# Peripheral.net
KiCad netlist of a schematic drawn in Altium Designer
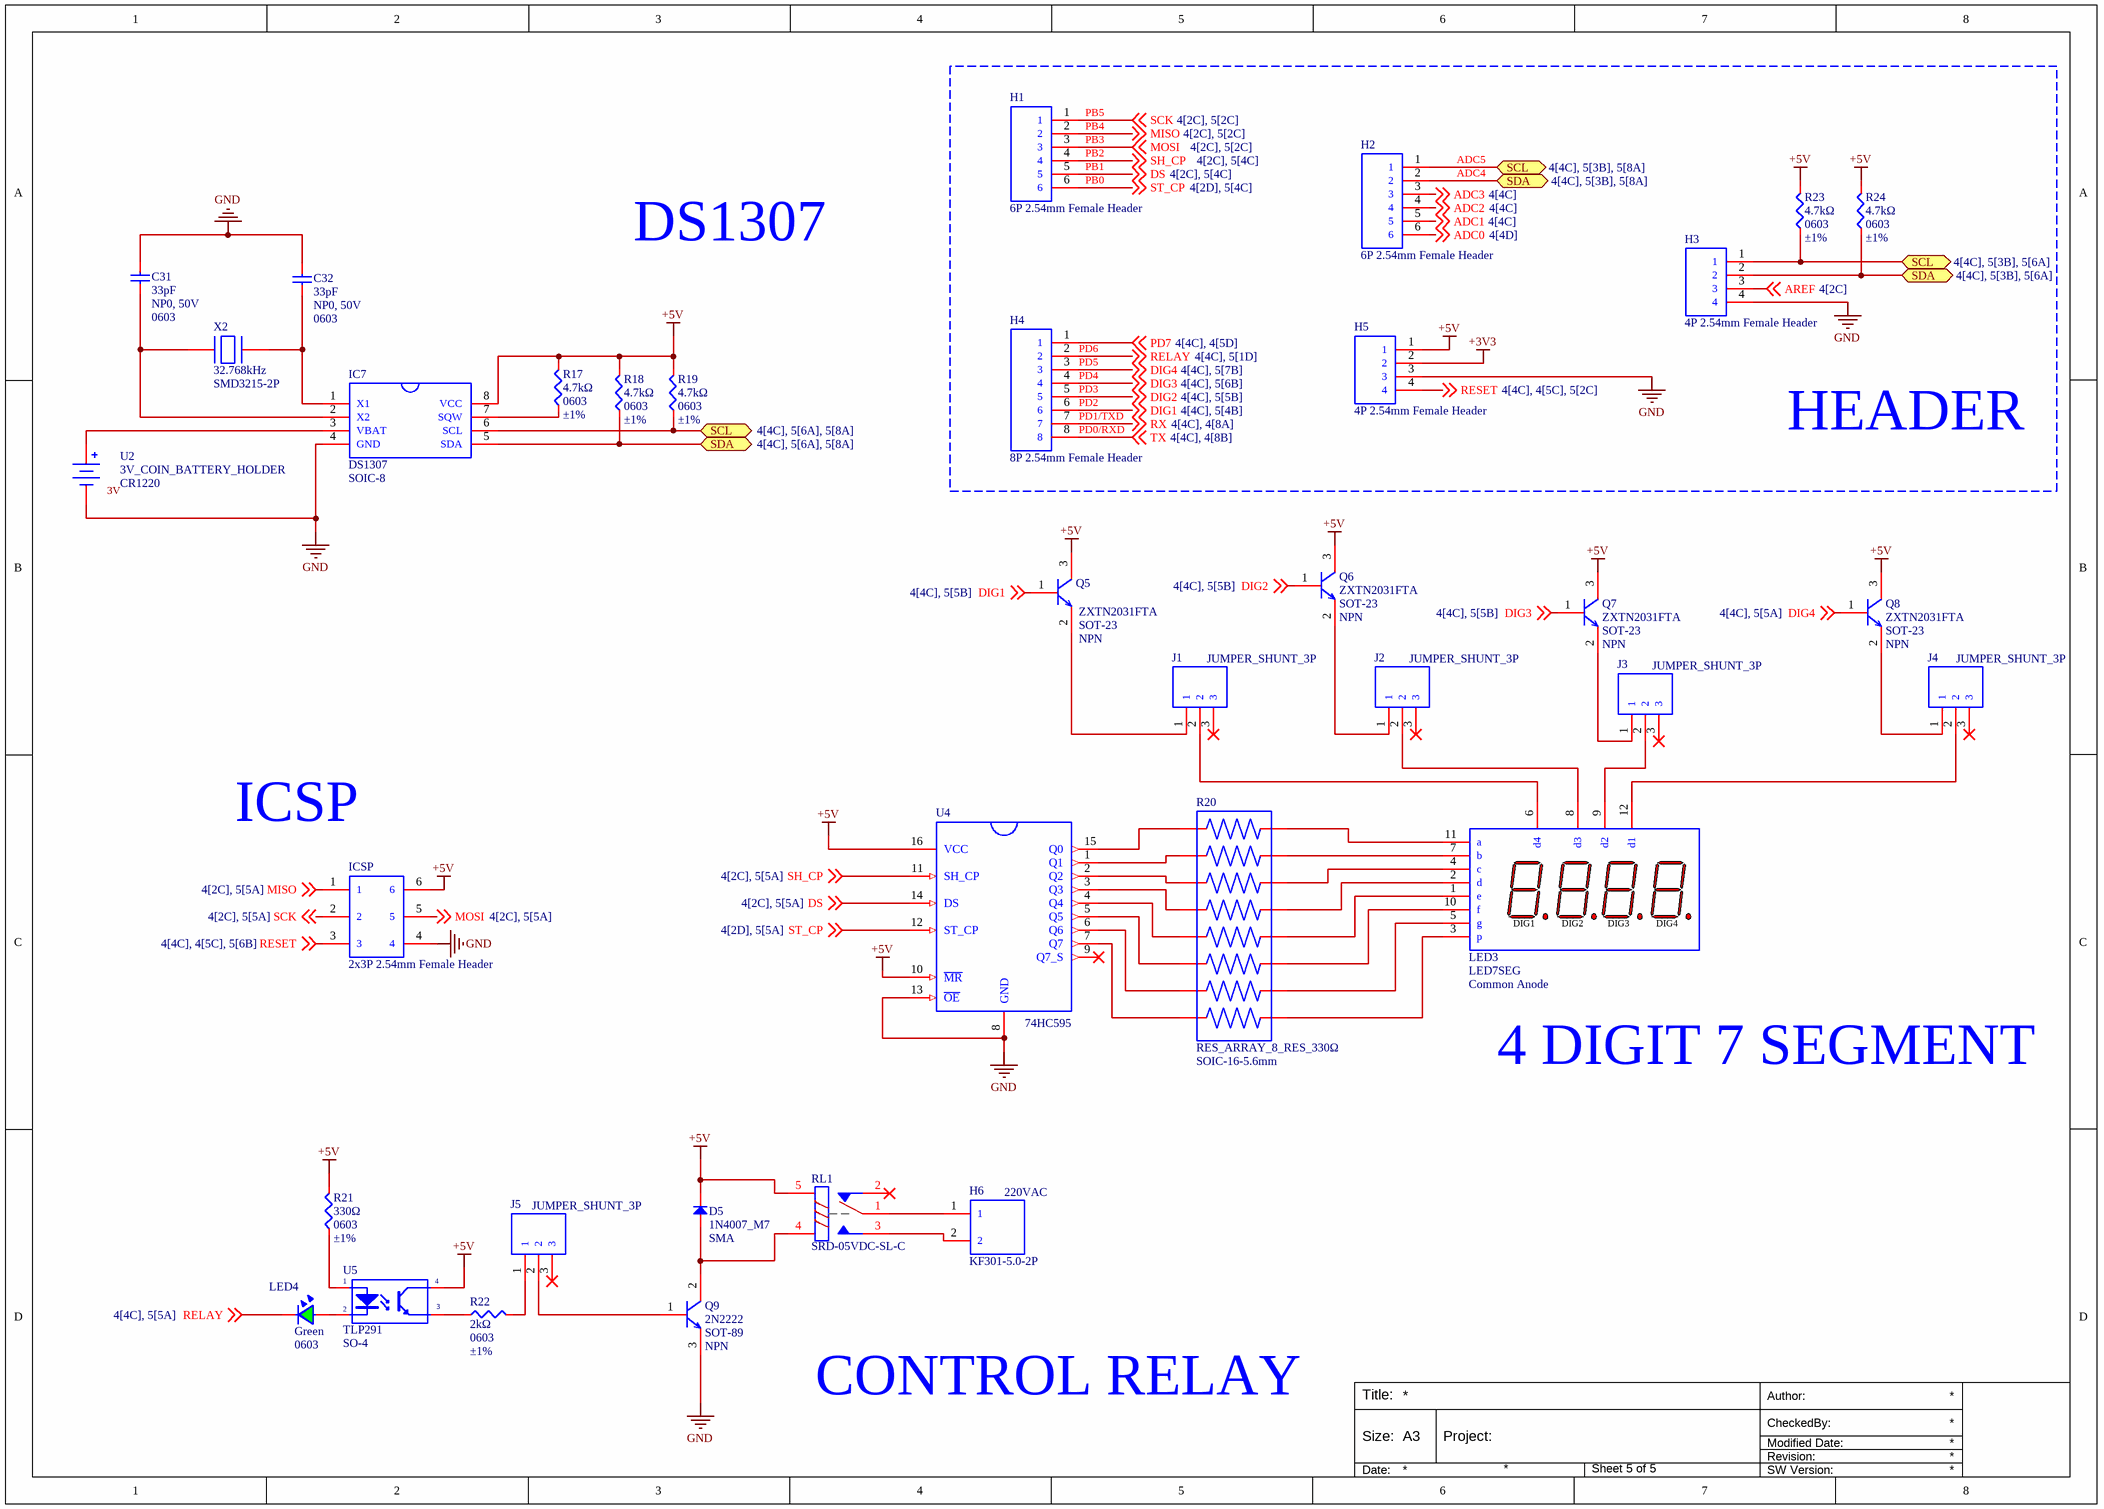
[diagram p0: Peripheral.SchDoc]

(export (version "E")
  (design (tool "Eeschema 10.0.6"))
  (components
    (comp (ref "C31")
      (value "33pF")
      (footprint "C0603")
      (description "50V 33pF NP0 ±5% 0603 Multilayer Ceramic Capacitors MLCC - SMD/SMT ROHS")
      (fields
        (field (name "MANUFACTURER") "YAGEO")
        (field (name "MFR. PART") "CC0603JRNPO9BN330")
        (field (name "TEMPERATURE COEFFICIENT") "NP0, 50V")
        (field (name "PACKAGE") "0603")
      )
      (libsource (lib "Capacitor") (part "C0603_MLCC_33pF_NP0_50V"))
    )
    (comp (ref "C32")
      (value "33pF")
      (footprint "C0603")
      (description "50V 33pF NP0 ±5% 0603 Multilayer Ceramic Capacitors MLCC - SMD/SMT ROHS")
      (fields
        (field (name "MANUFACTURER") "YAGEO")
        (field (name "MFR. PART") "CC0603JRNPO9BN330")
        (field (name "TEMPERATURE COEFFICIENT") "NP0, 50V")
        (field (name "PACKAGE") "0603")
      )
      (libsource (lib "Capacitor") (part "C0603_MLCC_33pF_NP0_50V"))
    )
    (comp (ref "D5")
      (value "1N4007_M7")
      (footprint "SMA(DO-214AC)")
      (description "1A 1V@1A 1kV SMA Diodes - General Purpose ROHS")
      (fields
        (field (name "MANUFACTURER") "JSMSEMI")
        (field (name "MFR. PART") "1N4007 M7")
        (field (name "PACKAGE") "SMA")
      )
      (libsource (lib "DIODE") (part "1N4007_M7"))
    )
    (comp (ref "H1")
      (value "6P 2.54mm Female Header")
      (footprint "6P, 2,54mm, FEMALE HEADER")
      (description "2.54mm 1 6P Through Hole 1x6P Through Hole,P=2.54mm Female Headers ROHS")
      (fields
        (field (name "MANUFACTURER") "BOOMELE(Boom Precision Elec)")
        (field (name "MFR. PART") "2.54-1*6P")
      )
      (libsource (lib "HEADER") (part "6P 2.54mm Female Header"))
    )
    (comp (ref "H2")
      (value "6P 2.54mm Female Header")
      (footprint "6P, 2,54mm, FEMALE HEADER")
      (description "2.54mm 1 6P Through Hole 1x6P Through Hole,P=2.54mm Female Headers ROHS")
      (fields
        (field (name "MANUFACTURER") "BOOMELE(Boom Precision Elec)")
        (field (name "MFR. PART") "2.54-1*6P")
      )
      (libsource (lib "HEADER") (part "6P 2.54mm Female Header"))
    )
    (comp (ref "H3")
      (value "4P 2.54mm Female Header")
      (footprint "4P, 2,54mm, FEMALE HEADER")
      (fields
        (field (name "MANUFACTURER") "BOOMELE(Boom Precision Elec)")
        (field (name "MFR. PART") "2.54-1*4P")
        (field (name "LCSC PART") "C2718488")
      )
      (libsource (lib "HEADER") (part "4P 2.54mm Female Header"))
    )
    (comp (ref "H4")
      (value "8P 2.54mm Female Header")
      (footprint "8P, 2,54mm, FEMALE HEADER")
      (description "2.54mm 1 8P Through Hole 1x8P Through Hole,P=2.54mm Female Headers ROHS")
      (fields
        (field (name "MANUFACTURER") "BOOMELE(Boom Precision Elec)")
        (field (name "MFR. PART") "2.54-1*8P")
      )
      (libsource (lib "HEADER") (part "8P 2.54mm Female Header"))
    )
    (comp (ref "H5")
      (value "4P 2.54mm Female Header")
      (footprint "4P, 2,54mm, FEMALE HEADER")
      (fields
        (field (name "MANUFACTURER") "BOOMELE(Boom Precision Elec)")
        (field (name "MFR. PART") "2.54-1*4P")
        (field (name "LCSC PART") "C2718488")
      )
      (libsource (lib "HEADER") (part "4P 2.54mm Female Header"))
    )
    (comp (ref "H6")
      (value "KF301-5.0-2P")
      (footprint "CONN-TH_P5.00_KF301-5.0-2P")
      (fields
        (field (name "MANUFACTURER") "Cixi Kefa Elec")
        (field (name "LCSC PART") "C474881")
        (field (name "CONFIGURE") "220VAC")
      )
      (libsource (lib "CONNECTER") (part "KF301-5.0-2P"))
    )
    (comp (ref "IC7")
      (value "DS1307")
      (footprint "SOIC-8")
      (description "I2C SOIC-8 Real Time Clocks ROHS")
      (fields
        (field (name "MANUFACTURER") "MAXIM")
        (field (name "MFR. PART") "DS1307Z+T&R")
        (field (name "PACKAGE") "SOIC-8")
      )
      (libsource (lib "IC") (part "DS1307-SOIC8"))
    )
    (comp (ref "ICSP")
      (value "2x3P 2.54mm Female Header")
      (footprint "2x3P, 2.54mm, Female Header")
      (fields
        (field (name "MANUFACTURER") "HanElectricity")
        (field (name "MFR. PART") "2541FV-2x3P")
        (field (name "LCSC PART") "C18723054")
      )
      (libsource (lib "HEADER") (part "2x3P 2.54mm Female Header"))
    )
    (comp (ref "J1")
      (value "JUMPER_SHUNT_3P")
      (footprint "JUMPER_SHUNT_3P")
      (fields
        (field (name "MANUFACTURER") "XFCN")
        (field (name "MFR. PART") "PZ254V-11-03P")
        (field (name "LCSC PART") "C2937625")
      )
      (libsource (lib "JUMP") (part "JUMPER_SHUNT_3P"))
    )
    (comp (ref "J2")
      (value "JUMPER_SHUNT_3P")
      (footprint "JUMPER_SHUNT_3P")
      (fields
        (field (name "MANUFACTURER") "XFCN")
        (field (name "MFR. PART") "PZ254V-11-03P")
        (field (name "LCSC PART") "C2937625")
      )
      (libsource (lib "JUMP") (part "JUMPER_SHUNT_3P"))
    )
    (comp (ref "J3")
      (value "JUMPER_SHUNT_3P")
      (footprint "JUMPER_SHUNT_3P")
      (fields
        (field (name "MANUFACTURER") "XFCN")
        (field (name "MFR. PART") "PZ254V-11-03P")
        (field (name "LCSC PART") "C2937625")
      )
      (libsource (lib "JUMP") (part "JUMPER_SHUNT_3P"))
    )
    (comp (ref "J4")
      (value "JUMPER_SHUNT_3P")
      (footprint "JUMPER_SHUNT_3P")
      (fields
        (field (name "MANUFACTURER") "XFCN")
        (field (name "MFR. PART") "PZ254V-11-03P")
        (field (name "LCSC PART") "C2937625")
      )
      (libsource (lib "JUMP") (part "JUMPER_SHUNT_3P"))
    )
    (comp (ref "J5")
      (value "JUMPER_SHUNT_3P")
      (footprint "JUMPER_SHUNT_3P")
      (fields
        (field (name "MANUFACTURER") "XFCN")
        (field (name "MFR. PART") "PZ254V-11-03P")
        (field (name "LCSC PART") "C2937625")
      )
      (libsource (lib "JUMP") (part "JUMPER_SHUNT_3P"))
    )
    (comp (ref "LED3")
      (value "LED7SEG")
      (footprint "LED7SEG_4")
      (description "Red 4 Common Anode 0.56 Through Hole LED Segment Displays ROHS")
      (fields
        (field (name "MANUFACTURER") "ZHIHAO")
        (field (name "MFR. PART") "FJ5461BH")
        (field (name "LED POLARITY") "Common Anode")
      )
      (libsource (lib "LED") (part "LED7SEG_Common_Anode"))
    )
    (comp (ref "LED4")
      (value "Green")
      (footprint "LED0603_GREEN")
      (fields
        (field (name "MANUFACTURER") "Kingbright")
        (field (name "MFR. PART") "KPT-1608LVZGCK")
        (field (name "LCSC PART") "C598356")
        (field (name "PACKAGE") "0603")
      )
      (libsource (lib "LED") (part "LED0603_Green"))
    )
    (comp (ref "Q5")
      (value "ZXTN2031FTA")
      (footprint "SOT-23")
      (description "50V 200@2A,2V 1.2W 5A NPN SOT-23 Bipolar (BJT) ROHS")
      (fields
        (field (name "MANUFACTURER") "DIODES")
        (field (name "LCSC PART") "C92166")
        (field (name "PACKAGE") "SOT-23")
        (field (name "TYPE") "NPN")
      )
      (libsource (lib "BJT and FET") (part "ZXTN2031FTA"))
    )
    (comp (ref "Q6")
      (value "ZXTN2031FTA")
      (footprint "SOT-23")
      (description "50V 200@2A,2V 1.2W 5A NPN SOT-23 Bipolar (BJT) ROHS")
      (fields
        (field (name "MANUFACTURER") "DIODES")
        (field (name "LCSC PART") "C92166")
        (field (name "PACKAGE") "SOT-23")
        (field (name "TYPE") "NPN")
      )
      (libsource (lib "BJT and FET") (part "ZXTN2031FTA"))
    )
    (comp (ref "Q7")
      (value "ZXTN2031FTA")
      (footprint "SOT-23")
      (description "50V 200@2A,2V 1.2W 5A NPN SOT-23 Bipolar (BJT) ROHS")
      (fields
        (field (name "MANUFACTURER") "DIODES")
        (field (name "LCSC PART") "C92166")
        (field (name "PACKAGE") "SOT-23")
        (field (name "TYPE") "NPN")
      )
      (libsource (lib "BJT and FET") (part "ZXTN2031FTA"))
    )
    (comp (ref "Q8")
      (value "ZXTN2031FTA")
      (footprint "SOT-23")
      (description "50V 200@2A,2V 1.2W 5A NPN SOT-23 Bipolar (BJT) ROHS")
      (fields
        (field (name "MANUFACTURER") "DIODES")
        (field (name "LCSC PART") "C92166")
        (field (name "PACKAGE") "SOT-23")
        (field (name "TYPE") "NPN")
      )
      (libsource (lib "BJT and FET") (part "ZXTN2031FTA"))
    )
    (comp (ref "Q9")
      (value "2N2222")
      (footprint "SOT-89-3L")
      (description "40V 500mW 600mA NPN SOT-89 Bipolar (BJT) ROHS")
      (fields
        (field (name "MANUFACTURER") "CBI")
        (field (name "MFR. PART") "2N2222AU")
        (field (name "PACKAGE") "SOT-89")
        (field (name "TYPE") "NPN")
      )
      (libsource (lib "BJT and FET") (part "2N2222_SOT-89"))
    )
    (comp (ref "R17")
      (value "4.7kΩ")
      (footprint "R0603")
      (description "100mW Thick Film Resistor 75V ±100ppm/℃ ±1% 4.7kΩ 0603 Chip Resistor - Surface Mount ROHS")
      (fields
        (field (name "MANUFACTURER") "YAGEO")
        (field (name "MFR. PART") "RC0603FR-074K7L")
        (field (name "PACKAGE") "0603")
        (field (name "TOLERANCE") "±1%")
      )
      (libsource (lib "Resistor") (part "R0603_4.7kΩ_±1%"))
    )
    (comp (ref "R18")
      (value "4.7kΩ")
      (footprint "R0603")
      (description "100mW Thick Film Resistor 75V ±100ppm/℃ ±1% 4.7kΩ 0603 Chip Resistor - Surface Mount ROHS")
      (fields
        (field (name "MANUFACTURER") "YAGEO")
        (field (name "MFR. PART") "RC0603FR-074K7L")
        (field (name "PACKAGE") "0603")
        (field (name "TOLERANCE") "±1%")
      )
      (libsource (lib "Resistor") (part "R0603_4.7kΩ_±1%"))
    )
    (comp (ref "R19")
      (value "4.7kΩ")
      (footprint "R0603")
      (description "100mW Thick Film Resistor 75V ±100ppm/℃ ±1% 4.7kΩ 0603 Chip Resistor - Surface Mount ROHS")
      (fields
        (field (name "MANUFACTURER") "YAGEO")
        (field (name "MFR. PART") "RC0603FR-074K7L")
        (field (name "PACKAGE") "0603")
        (field (name "TOLERANCE") "±1%")
      )
      (libsource (lib "Resistor") (part "R0603_4.7kΩ_±1%"))
    )
    (comp (ref "R20")
      (value "RES_ARRAY_8_RES_330Ω")
      (footprint "SOIC-16-5.6mm")
      (description "8 ±2% 330Ω 160mW ±100ppm/℃ SOIC-16-5.6mm Resistor Networks, Arrays ROHS")
      (fields
        (field (name "MANUFACTURER") "BOURNS")
        (field (name "TOLERANCE") "±2%")
        (field (name "PACKAGE") "SOIC-16-5.6mm")
      )
      (libsource (lib "Resistor") (part "RES_ARRAY_8_RES_330Ω"))
    )
    (comp (ref "R21")
      (value "330Ω")
      (footprint "R0603")
      (description "100mW Thick Film Resistor 75V ±100ppm/℃ ±1% 330Ω 0603 Chip Resistor - Surface Mount ROHS")
      (fields
        (field (name "MANUFACTURER") "YAGEO")
        (field (name "MFR. PART") "RC0603FR-07330RL")
        (field (name "PACKAGE") "0603")
        (field (name "TOLERANCE") "±1%")
      )
      (libsource (lib "Resistor") (part "R0603_330Ω_±1%"))
    )
    (comp (ref "R22")
      (value "2kΩ")
      (footprint "R0603")
      (description "100mW Thick Film Resistor 75V ±100ppm/℃ ±1% 2kΩ 0603 Chip Resistor - Surface Mount ROHS")
      (fields
        (field (name "MANUFACTURER") "YAGEO")
        (field (name "MFR. PART") "RC0603FR-072KL")
        (field (name "PACKAGE") "0603")
        (field (name "TOLERANCE") "±1%")
      )
      (libsource (lib "Resistor") (part "R0603_2kΩ_±1%"))
    )
    (comp (ref "R23")
      (value "4.7kΩ")
      (footprint "R0603")
      (description "100mW Thick Film Resistor 75V ±100ppm/℃ ±1% 4.7kΩ 0603 Chip Resistor - Surface Mount ROHS")
      (fields
        (field (name "MANUFACTURER") "YAGEO")
        (field (name "MFR. PART") "RC0603FR-074K7L")
        (field (name "PACKAGE") "0603")
        (field (name "TOLERANCE") "±1%")
      )
      (libsource (lib "Resistor") (part "R0603_4.7kΩ_±1%"))
    )
    (comp (ref "R24")
      (value "4.7kΩ")
      (footprint "R0603")
      (description "100mW Thick Film Resistor 75V ±100ppm/℃ ±1% 4.7kΩ 0603 Chip Resistor - Surface Mount ROHS")
      (fields
        (field (name "MANUFACTURER") "YAGEO")
        (field (name "MFR. PART") "RC0603FR-074K7L")
        (field (name "PACKAGE") "0603")
        (field (name "TOLERANCE") "±1%")
      )
      (libsource (lib "Resistor") (part "R0603_4.7kΩ_±1%"))
    )
    (comp (ref "RL1")
      (value "SRD-05VDC-SL-C")
      (footprint "Through Hole,15.6x19.2mm")
      (description "250V@AC 5V 15A 1 Form C: 1C (SPDT-CO) Through Hole,15.6x19.2mm Power Relays ROHS")
      (fields (field (name "MANUFACTURER") "Songle Relay") (field (name "LCSC PART") "C35449"))
      (libsource (lib "RELAY") (part "SRD-05VDC-SL-C"))
    )
    (comp (ref "U2")
      (value "3V_COIN_BATTERY_HOLDER")
      (footprint "3V_COIN_BATERRY_HOLDER_CR1220")
      (description "Battery Holder -25℃~+85℃ Phosphor Bronze CR1220 SMD Button And Strip Battery Connector ROHS")
      (fields
        (field (name "MANUFACTURER") "MYOUNG")
        (field (name "LCSC PART") "C964723")
        (field (name "BATTERY TYPE") "CR1220")
      )
      (libsource (lib "PIN") (part "3V_COIN_BATTERY_HOLDER"))
    )
    (comp (ref "U4")
      (value "74HC595")
      (footprint "TSSOP16")
      (description "8 2V~6V 1 Serial-to-Serial or Parallel TSSOP-16 Shift Registers ROHS")
      (fields (field (name "MANUFACTURER") "Nexperia") (field (name "MFR. PART") "74HC595PW,118"))
      (libsource (lib "IC") (part "74HC595"))
    )
    (comp (ref "U5")
      (value "TLP291")
      (footprint "SO-4")
      (description "SO-4 Transistor, Photovoltaic Output Optoisolators ROHS")
      (fields
        (field (name "MANUFACTURER") "TOSHIBA")
        (field (name "MFR. PART") "TLP291(GB-TP,SE(T")
        (field (name "PACKAGE") "SO-4")
      )
      (libsource (lib "OPTO") (part "TLP291"))
    )
    (comp (ref "X2")
      (value "32.768kHz")
      (footprint "SMD3215-2P")
      (description "32.768kHz 12.5pF ±20ppm SMD3215-2P Crystals ROHS")
      (fields
        (field (name "MANUFACTURER") "NDK")
        (field (name "MFR. PART") "NX3215SA-32.768K-STD-MUA-8")
        (field (name "PACKAGE") "SMD3215-2P")
      )
      (libsource (lib "CRYSTAL") (part "Crystal_32.768Khz"))
    )
  )
  (nets
    (net (code "1") (name "+3V3") (class "Default")
      (node (ref "H5") (pin "2") (pinfunction "2_2") (pintype "passive"))
    )
    (net (code "2") (name "+5V") (class "Default")
      (node (ref "D5") (pin "1") (pinfunction "1_1") (pintype "passive"))
      (node (ref "H5") (pin "1") (pinfunction "1_1") (pintype "passive"))
      (node (ref "IC7") (pin "8") (pinfunction "VCC_8") (pintype "passive"))
      (node (ref "ICSP") (pin "6") (pinfunction "6_6") (pintype "passive"))
      (node (ref "Q5") (pin "3") (pinfunction "C_3") (pintype "passive"))
      (node (ref "Q6") (pin "3") (pinfunction "C_3") (pintype "passive"))
      (node (ref "Q7") (pin "3") (pinfunction "C_3") (pintype "passive"))
      (node (ref "Q8") (pin "3") (pinfunction "C_3") (pintype "passive"))
      (node (ref "R17") (pin "2") (pinfunction "2_2") (pintype "passive"))
      (node (ref "R18") (pin "2") (pinfunction "2_2") (pintype "passive"))
      (node (ref "R19") (pin "2") (pinfunction "2_2") (pintype "passive"))
      (node (ref "R21") (pin "2") (pinfunction "2_2") (pintype "passive"))
      (node (ref "R23") (pin "2") (pinfunction "2_2") (pintype "passive"))
      (node (ref "R24") (pin "2") (pinfunction "2_2") (pintype "passive"))
      (node (ref "RL1") (pin "5") (pinfunction "5_5") (pintype "passive"))
      (node (ref "U4") (pin "10") (pinfunction "~{MR}_10") (pintype "input"))
      (node (ref "U4") (pin "16") (pinfunction "VCC_16") (pintype "power_in"))
      (node (ref "U5") (pin "4") (pinfunction "C_4") (pintype "passive"))
    )
    (net (code "3") (name "/SCL") (class "Default")
      (node (ref "H2") (pin "1") (pinfunction "1_1") (pintype "passive"))
      (node (ref "H3") (pin "1") (pinfunction "1_1") (pintype "passive"))
      (node (ref "IC7") (pin "6") (pinfunction "SCL_6") (pintype "passive"))
      (node (ref "R19") (pin "1") (pinfunction "1_1") (pintype "passive"))
      (node (ref "R23") (pin "1") (pinfunction "1_1") (pintype "passive"))
    )
    (net (code "4") (name "/SDA") (class "Default")
      (node (ref "H2") (pin "2") (pinfunction "2_2") (pintype "passive"))
      (node (ref "H3") (pin "2") (pinfunction "2_2") (pintype "passive"))
      (node (ref "IC7") (pin "5") (pinfunction "SDA_5") (pintype "passive"))
      (node (ref "R18") (pin "1") (pinfunction "1_1") (pintype "passive"))
      (node (ref "R24") (pin "1") (pinfunction "1_1") (pintype "passive"))
    )
    (net (code "5") (name "ADC0") (class "Default")
      (node (ref "H2") (pin "6") (pinfunction "6_6") (pintype "passive"))
    )
    (net (code "6") (name "ADC1") (class "Default")
      (node (ref "H2") (pin "5") (pinfunction "5_5") (pintype "passive"))
    )
    (net (code "7") (name "ADC2") (class "Default")
      (node (ref "H2") (pin "4") (pinfunction "4_4") (pintype "passive"))
    )
    (net (code "8") (name "ADC3") (class "Default")
      (node (ref "H2") (pin "3") (pinfunction "3_3") (pintype "passive"))
    )
    (net (code "9") (name "AREF") (class "Default")
      (node (ref "H3") (pin "3") (pinfunction "3_3") (pintype "passive"))
    )
    (net (code "10") (name "DIG1") (class "Default")
      (node (ref "H4") (pin "6") (pinfunction "6_6") (pintype "passive"))
      (node (ref "Q5") (pin "1") (pinfunction "B_1") (pintype "passive"))
    )
    (net (code "11") (name "DIG2") (class "Default")
      (node (ref "H4") (pin "5") (pinfunction "5_5") (pintype "passive"))
      (node (ref "Q6") (pin "1") (pinfunction "B_1") (pintype "passive"))
    )
    (net (code "12") (name "DIG3") (class "Default")
      (node (ref "H4") (pin "4") (pinfunction "4_4") (pintype "passive"))
      (node (ref "Q7") (pin "1") (pinfunction "B_1") (pintype "passive"))
    )
    (net (code "13") (name "DIG4") (class "Default")
      (node (ref "H4") (pin "3") (pinfunction "3_3") (pintype "passive"))
      (node (ref "Q8") (pin "1") (pinfunction "B_1") (pintype "passive"))
    )
    (net (code "14") (name "DS") (class "Default")
      (node (ref "H1") (pin "5") (pinfunction "5_5") (pintype "passive"))
      (node (ref "U4") (pin "14") (pinfunction "DS_14") (pintype "input"))
    )
    (net (code "15") (name "GND") (class "Default")
      (node (ref "C31") (pin "2") (pinfunction "2_2") (pintype "passive"))
      (node (ref "C32") (pin "2") (pinfunction "2_2") (pintype "passive"))
      (node (ref "H3") (pin "4") (pinfunction "4_4") (pintype "passive"))
      (node (ref "H5") (pin "3") (pinfunction "3_3") (pintype "passive"))
      (node (ref "IC7") (pin "4") (pinfunction "GND_4") (pintype "passive"))
      (node (ref "ICSP") (pin "4") (pinfunction "4_4") (pintype "passive"))
      (node (ref "Q9") (pin "3") (pinfunction "E_3") (pintype "passive"))
      (node (ref "U2") (pin "2") (pinfunction "2_2") (pintype "passive"))
      (node (ref "U4") (pin "13") (pinfunction "~{OE}_13") (pintype "input"))
      (node (ref "U4") (pin "8") (pinfunction "GND_8") (pintype "passive"))
    )
    (net (code "16") (name "MISO") (class "Default")
      (node (ref "H1") (pin "2") (pinfunction "2_2") (pintype "passive"))
      (node (ref "ICSP") (pin "1") (pinfunction "1_1") (pintype "passive"))
    )
    (net (code "17") (name "MOSI") (class "Default")
      (node (ref "H1") (pin "3") (pinfunction "3_3") (pintype "passive"))
      (node (ref "ICSP") (pin "5") (pinfunction "5_5") (pintype "passive"))
    )
    (net (code "18") (name "Net-(H6-Pad1)") (class "Default")
      (node (ref "H6") (pin "1") (pinfunction "1_1") (pintype "passive"))
      (node (ref "RL1") (pin "1") (pinfunction "1_1") (pintype "passive"))
    )
    (net (code "19") (name "Net-(H6-Pad2)") (class "Default")
      (node (ref "H6") (pin "2") (pinfunction "2_2") (pintype "passive"))
      (node (ref "RL1") (pin "3") (pinfunction "3_3") (pintype "passive"))
    )
    (net (code "20") (name "Net-(IC7-SQW)") (class "Default")
      (node (ref "IC7") (pin "7") (pinfunction "SQW_7") (pintype "passive"))
      (node (ref "R17") (pin "1") (pinfunction "1_1") (pintype "passive"))
    )
    (net (code "21") (name "Net-(IC7-VBAT)") (class "Default")
      (node (ref "IC7") (pin "3") (pinfunction "VBAT_3") (pintype "passive"))
      (node (ref "U2") (pin "1") (pinfunction "1_1") (pintype "passive"))
    )
    (net (code "22") (name "Net-(IC7-X1)") (class "Default")
      (node (ref "C32") (pin "1") (pinfunction "1_1") (pintype "passive"))
      (node (ref "IC7") (pin "1") (pinfunction "X1_1") (pintype "passive"))
      (node (ref "X2") (pin "1") (pinfunction "1_1") (pintype "passive"))
    )
    (net (code "23") (name "Net-(IC7-X2)") (class "Default")
      (node (ref "C31") (pin "1") (pinfunction "1_1") (pintype "passive"))
      (node (ref "IC7") (pin "2") (pinfunction "X2_2") (pintype "passive"))
      (node (ref "X2") (pin "2") (pinfunction "2_2") (pintype "passive"))
    )
    (net (code "24") (name "Net-(J5-Pad1)") (class "Default")
      (node (ref "J5") (pin "1") (pinfunction "1_1") (pintype "passive"))
      (node (ref "R22") (pin "2") (pinfunction "2_2") (pintype "passive"))
    )
    (net (code "25") (name "Net-(LED3-a)") (class "Default")
      (node (ref "LED3") (pin "11") (pinfunction "a_11") (pintype "passive"))
      (node (ref "R20") (pin "16") (pinfunction "16_16") (pintype "passive"))
    )
    (net (code "26") (name "Net-(LED3-b)") (class "Default")
      (node (ref "LED3") (pin "7") (pinfunction "b_7") (pintype "passive"))
      (node (ref "R20") (pin "15") (pinfunction "15_15") (pintype "passive"))
    )
    (net (code "27") (name "Net-(LED3-c)") (class "Default")
      (node (ref "LED3") (pin "4") (pinfunction "c_4") (pintype "passive"))
      (node (ref "R20") (pin "14") (pinfunction "14_14") (pintype "passive"))
    )
    (net (code "28") (name "Net-(LED3-d)") (class "Default")
      (node (ref "LED3") (pin "2") (pinfunction "d_2") (pintype "passive"))
      (node (ref "R20") (pin "13") (pinfunction "13_13") (pintype "passive"))
    )
    (net (code "29") (name "Net-(LED3-d1)") (class "Default")
      (node (ref "J4") (pin "2") (pinfunction "2_2") (pintype "passive"))
      (node (ref "LED3") (pin "12") (pinfunction "d1_12") (pintype "passive"))
    )
    (net (code "30") (name "Net-(LED3-d2)") (class "Default")
      (node (ref "J3") (pin "2") (pinfunction "2_2") (pintype "passive"))
      (node (ref "LED3") (pin "9") (pinfunction "d2_9") (pintype "passive"))
    )
    (net (code "31") (name "Net-(LED3-d3)") (class "Default")
      (node (ref "J2") (pin "2") (pinfunction "2_2") (pintype "passive"))
      (node (ref "LED3") (pin "8") (pinfunction "d3_8") (pintype "passive"))
    )
    (net (code "32") (name "Net-(LED3-d4)") (class "Default")
      (node (ref "J1") (pin "2") (pinfunction "2_2") (pintype "passive"))
      (node (ref "LED3") (pin "6") (pinfunction "d4_6") (pintype "passive"))
    )
    (net (code "33") (name "Net-(LED3-e)") (class "Default")
      (node (ref "LED3") (pin "1") (pinfunction "e_1") (pintype "passive"))
      (node (ref "R20") (pin "12") (pinfunction "12_12") (pintype "passive"))
    )
    (net (code "34") (name "Net-(LED3-f)") (class "Default")
      (node (ref "LED3") (pin "10") (pinfunction "f_10") (pintype "passive"))
      (node (ref "R20") (pin "11") (pinfunction "11_11") (pintype "passive"))
    )
    (net (code "35") (name "Net-(LED3-g)") (class "Default")
      (node (ref "LED3") (pin "5") (pinfunction "g_5") (pintype "passive"))
      (node (ref "R20") (pin "10") (pinfunction "10_10") (pintype "passive"))
    )
    (net (code "36") (name "Net-(LED3-p)") (class "Default")
      (node (ref "LED3") (pin "3") (pinfunction "p_3") (pintype "passive"))
      (node (ref "R20") (pin "9") (pinfunction "9_9") (pintype "passive"))
    )
    (net (code "37") (name "Net-(Q5-E)") (class "Default")
      (node (ref "J1") (pin "1") (pinfunction "1_1") (pintype "passive"))
      (node (ref "Q5") (pin "2") (pinfunction "E_2") (pintype "passive"))
    )
    (net (code "38") (name "Net-(Q6-E)") (class "Default")
      (node (ref "J2") (pin "1") (pinfunction "1_1") (pintype "passive"))
      (node (ref "Q6") (pin "2") (pinfunction "E_2") (pintype "passive"))
    )
    (net (code "39") (name "Net-(Q7-E)") (class "Default")
      (node (ref "J3") (pin "1") (pinfunction "1_1") (pintype "passive"))
      (node (ref "Q7") (pin "2") (pinfunction "E_2") (pintype "passive"))
    )
    (net (code "40") (name "Net-(Q8-E)") (class "Default")
      (node (ref "J4") (pin "1") (pinfunction "1_1") (pintype "passive"))
      (node (ref "Q8") (pin "2") (pinfunction "E_2") (pintype "passive"))
    )
    (net (code "41") (name "Net-(Q9-B)") (class "Default")
      (node (ref "J5") (pin "2") (pinfunction "2_2") (pintype "passive"))
      (node (ref "Q9") (pin "1") (pinfunction "B_1") (pintype "passive"))
    )
    (net (code "42") (name "Net-(Q9-C)") (class "Default")
      (node (ref "D5") (pin "2") (pinfunction "2_2") (pintype "passive"))
      (node (ref "Q9") (pin "2") (pinfunction "C_2") (pintype "passive"))
      (node (ref "RL1") (pin "4") (pinfunction "4_4") (pintype "passive"))
    )
    (net (code "43") (name "Net-(U4-Q0)") (class "Default")
      (node (ref "R20") (pin "1") (pinfunction "1_1") (pintype "passive"))
      (node (ref "U4") (pin "15") (pinfunction "Q0_15") (pintype "output"))
    )
    (net (code "44") (name "Net-(U4-Q1)") (class "Default")
      (node (ref "R20") (pin "2") (pinfunction "2_2") (pintype "passive"))
      (node (ref "U4") (pin "1") (pinfunction "Q1_1") (pintype "output"))
    )
    (net (code "45") (name "Net-(U4-Q2)") (class "Default")
      (node (ref "R20") (pin "3") (pinfunction "3_3") (pintype "passive"))
      (node (ref "U4") (pin "2") (pinfunction "Q2_2") (pintype "output"))
    )
    (net (code "46") (name "Net-(U4-Q3)") (class "Default")
      (node (ref "R20") (pin "4") (pinfunction "4_4") (pintype "passive"))
      (node (ref "U4") (pin "3") (pinfunction "Q3_3") (pintype "output"))
    )
    (net (code "47") (name "Net-(U4-Q4)") (class "Default")
      (node (ref "R20") (pin "5") (pinfunction "5_5") (pintype "passive"))
      (node (ref "U4") (pin "4") (pinfunction "Q4_4") (pintype "output"))
    )
    (net (code "48") (name "Net-(U4-Q5)") (class "Default")
      (node (ref "R20") (pin "6") (pinfunction "6_6") (pintype "passive"))
      (node (ref "U4") (pin "5") (pinfunction "Q5_5") (pintype "output"))
    )
    (net (code "49") (name "Net-(U4-Q6)") (class "Default")
      (node (ref "R20") (pin "7") (pinfunction "7_7") (pintype "passive"))
      (node (ref "U4") (pin "6") (pinfunction "Q6_6") (pintype "output"))
    )
    (net (code "50") (name "Net-(U4-Q7)") (class "Default")
      (node (ref "R20") (pin "8") (pinfunction "8_8") (pintype "passive"))
      (node (ref "U4") (pin "7") (pinfunction "Q7_7") (pintype "output"))
    )
    (net (code "51") (name "Net-(U5-A)") (class "Default")
      (node (ref "R21") (pin "1") (pinfunction "1_1") (pintype "passive"))
      (node (ref "U5") (pin "1") (pinfunction "A_1") (pintype "passive"))
    )
    (net (code "52") (name "Net-(U5-E)") (class "Default")
      (node (ref "R22") (pin "1") (pinfunction "1_1") (pintype "passive"))
      (node (ref "U5") (pin "3") (pinfunction "E_3") (pintype "passive"))
    )
    (net (code "53") (name "Net-(U5-K)") (class "Default")
      (node (ref "LED4") (pin "1") (pinfunction "1_1") (pintype "passive"))
      (node (ref "U5") (pin "2") (pinfunction "K_2") (pintype "passive"))
    )
    (net (code "54") (name "PD7") (class "Default")
      (node (ref "H4") (pin "1") (pinfunction "1_1") (pintype "passive"))
    )
    (net (code "55") (name "RELAY") (class "Default")
      (node (ref "H4") (pin "2") (pinfunction "2_2") (pintype "passive"))
      (node (ref "LED4") (pin "2") (pinfunction "2_2") (pintype "passive"))
    )
    (net (code "56") (name "RESET") (class "Default")
      (node (ref "H5") (pin "4") (pinfunction "4_4") (pintype "passive"))
      (node (ref "ICSP") (pin "3") (pinfunction "3_3") (pintype "passive"))
    )
    (net (code "57") (name "RX") (class "Default")
      (node (ref "H4") (pin "7") (pinfunction "7_7") (pintype "passive"))
    )
    (net (code "58") (name "SCK") (class "Default")
      (node (ref "H1") (pin "1") (pinfunction "1_1") (pintype "passive"))
      (node (ref "ICSP") (pin "2") (pinfunction "2_2") (pintype "passive"))
    )
    (net (code "59") (name "SH_CP") (class "Default")
      (node (ref "H1") (pin "4") (pinfunction "4_4") (pintype "passive"))
      (node (ref "U4") (pin "11") (pinfunction "SH_CP_11") (pintype "input"))
    )
    (net (code "60") (name "ST_CP") (class "Default")
      (node (ref "H1") (pin "6") (pinfunction "6_6") (pintype "passive"))
      (node (ref "U4") (pin "12") (pinfunction "ST_CP_12") (pintype "input"))
    )
    (net (code "61") (name "TX") (class "Default")
      (node (ref "H4") (pin "8") (pinfunction "8_8") (pintype "passive"))
    )
    (net (code "62") (name "unconnected-(J1-Pad3)") (class "Default")
      (node (ref "J1") (pin "3") (pinfunction "3_3") (pintype "passive+no_connect"))
    )
    (net (code "63") (name "unconnected-(J2-Pad3)") (class "Default")
      (node (ref "J2") (pin "3") (pinfunction "3_3") (pintype "passive+no_connect"))
    )
    (net (code "64") (name "unconnected-(J3-Pad3)") (class "Default")
      (node (ref "J3") (pin "3") (pinfunction "3_3") (pintype "passive+no_connect"))
    )
    (net (code "65") (name "unconnected-(J4-Pad3)") (class "Default")
      (node (ref "J4") (pin "3") (pinfunction "3_3") (pintype "passive+no_connect"))
    )
    (net (code "66") (name "unconnected-(J5-Pad3)") (class "Default")
      (node (ref "J5") (pin "3") (pinfunction "3_3") (pintype "passive+no_connect"))
    )
    (net (code "67") (name "unconnected-(RL1-Pad2)") (class "Default")
      (node (ref "RL1") (pin "2") (pinfunction "2_2") (pintype "passive+no_connect"))
    )
    (net (code "68") (name "unconnected-(U4-Q7_S-Pad9)") (class "Default")
      (node (ref "U4") (pin "9") (pinfunction "Q7_S_9") (pintype "output+no_connect"))
    )
  )
)
